# Board.net
KiCad netlist of a schematic drawn in Altium Designer
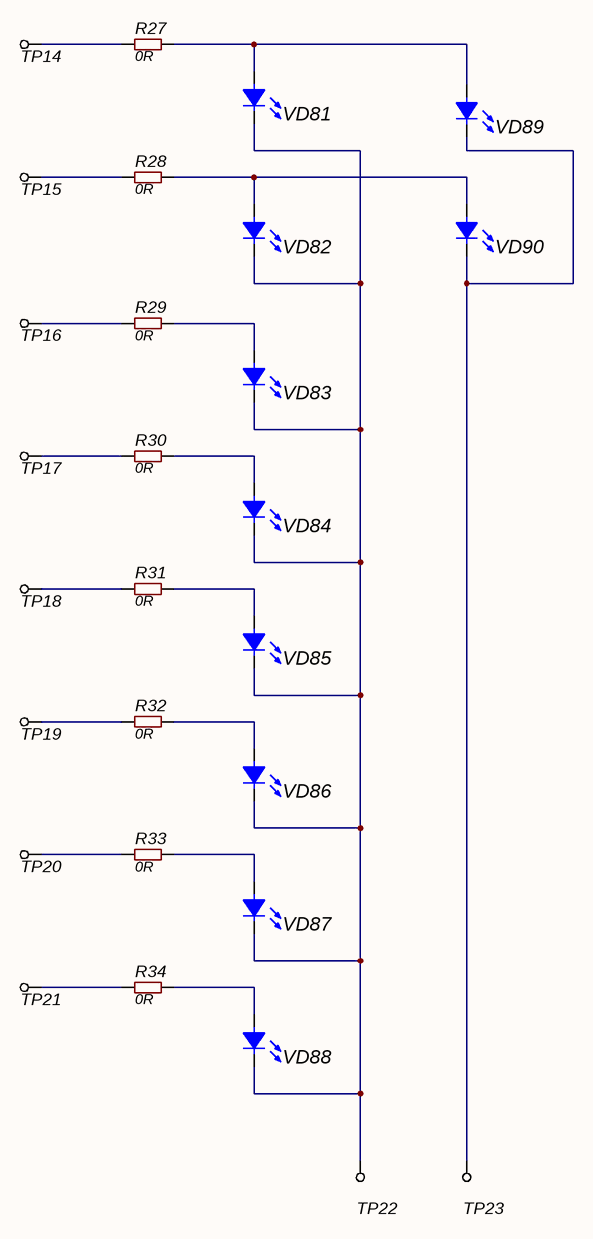
[diagram p0: Board.SchDoc]

(export (version "E")
  (design (tool "Eeschema 10.0.6"))
  (components
    (comp (ref "R27")
      (value "0R")
      (footprint "RES: 0603")
      (fields
        (field (name "MANUFACTURER") "Yageo")
        (field (name "PARTNUMBER") "RC0603JR-07100RL")
        (field (name "VALUEMANUFACTURERPARTNUMBER") "Resistor film, 0R, , 0603, 0.1W, -55...+125°C")
      )
      (libsource (lib "resistor") (part "Resistor_0603"))
    )
    (comp (ref "R28")
      (value "0R")
      (footprint "RES: 0603")
      (fields
        (field (name "MANUFACTURER") "Yageo")
        (field (name "PARTNUMBER") "RC0603JR-07100RL")
        (field (name "VALUEMANUFACTURERPARTNUMBER") "Resistor film, 0R, , 0603, 0.1W, -55...+125°C")
      )
      (libsource (lib "resistor") (part "Resistor_0603"))
    )
    (comp (ref "R29")
      (value "0R")
      (footprint "RES: 0603")
      (fields
        (field (name "MANUFACTURER") "Yageo")
        (field (name "PARTNUMBER") "RC0603JR-07100RL")
        (field (name "VALUEMANUFACTURERPARTNUMBER") "Resistor film, 0R, , 0603, 0.1W, -55...+125°C")
      )
      (libsource (lib "resistor") (part "Resistor_0603"))
    )
    (comp (ref "R30")
      (value "0R")
      (footprint "RES: 0603")
      (fields
        (field (name "MANUFACTURER") "Yageo")
        (field (name "PARTNUMBER") "RC0603JR-07100RL")
        (field (name "VALUEMANUFACTURERPARTNUMBER") "Resistor film, 0R, , 0603, 0.1W, -55...+125°C")
      )
      (libsource (lib "resistor") (part "Resistor_0603"))
    )
    (comp (ref "R31")
      (value "0R")
      (footprint "RES: 0603")
      (fields
        (field (name "MANUFACTURER") "Yageo")
        (field (name "PARTNUMBER") "RC0603JR-07100RL")
        (field (name "VALUEMANUFACTURERPARTNUMBER") "Resistor film, 0R, , 0603, 0.1W, -55...+125°C")
      )
      (libsource (lib "resistor") (part "Resistor_0603"))
    )
    (comp (ref "R32")
      (value "0R")
      (footprint "RES: 0603")
      (fields
        (field (name "MANUFACTURER") "Yageo")
        (field (name "PARTNUMBER") "RC0603JR-07100RL")
        (field (name "VALUEMANUFACTURERPARTNUMBER") "Resistor film, 0R, , 0603, 0.1W, -55...+125°C")
      )
      (libsource (lib "resistor") (part "Resistor_0603"))
    )
    (comp (ref "R33")
      (value "0R")
      (footprint "RES: 0603")
      (fields
        (field (name "MANUFACTURER") "Yageo")
        (field (name "PARTNUMBER") "RC0603JR-07100RL")
        (field (name "VALUEMANUFACTURERPARTNUMBER") "Resistor film, 0R, , 0603, 0.1W, -55...+125°C")
      )
      (libsource (lib "resistor") (part "Resistor_0603"))
    )
    (comp (ref "R34")
      (value "0R")
      (footprint "RES: 0603")
      (fields
        (field (name "MANUFACTURER") "Yageo")
        (field (name "PARTNUMBER") "RC0603JR-07100RL")
        (field (name "VALUEMANUFACTURERPARTNUMBER") "Resistor film, 0R, , 0603, 0.1W, -55...+125°C")
      )
      (libsource (lib "resistor") (part "Resistor_0603"))
    )
    (comp (ref "TP14")
      (value "Testpoint_HS1mm")
      (footprint "TestPoint(without 3D)")
      (libsource (lib "connector") (part "Testpoint_HS1mm"))
    )
    (comp (ref "TP15")
      (value "Testpoint_HS1mm")
      (footprint "TestPoint(without 3D)")
      (libsource (lib "connector") (part "Testpoint_HS1mm"))
    )
    (comp (ref "TP16")
      (value "Testpoint_HS1mm")
      (footprint "TestPoint(without 3D)")
      (libsource (lib "connector") (part "Testpoint_HS1mm"))
    )
    (comp (ref "TP17")
      (value "Testpoint_HS1mm")
      (footprint "TestPoint(without 3D)")
      (libsource (lib "connector") (part "Testpoint_HS1mm"))
    )
    (comp (ref "TP18")
      (value "Testpoint_HS1mm")
      (footprint "TestPoint(without 3D)")
      (libsource (lib "connector") (part "Testpoint_HS1mm"))
    )
    (comp (ref "TP19")
      (value "Testpoint_HS1mm")
      (footprint "TestPoint(without 3D)")
      (libsource (lib "connector") (part "Testpoint_HS1mm"))
    )
    (comp (ref "TP20")
      (value "Testpoint_HS1mm")
      (footprint "TestPoint(without 3D)")
      (libsource (lib "connector") (part "Testpoint_HS1mm"))
    )
    (comp (ref "TP21")
      (value "Testpoint_HS1mm")
      (footprint "TestPoint(without 3D)")
      (libsource (lib "connector") (part "Testpoint_HS1mm"))
    )
    (comp (ref "TP22")
      (value "Testpoint_HS1mm")
      (footprint "TestPoint(without 3D)")
      (libsource (lib "connector") (part "Testpoint_HS1mm"))
    )
    (comp (ref "TP23")
      (value "Testpoint_HS1mm")
      (footprint "TestPoint(without 3D)")
      (libsource (lib "connector") (part "Testpoint_HS1mm"))
    )
    (comp (ref "VD81")
      (value "~")
      (footprint "LED: 1206Y")
      (fields (field (name "VALUEMANUFACTURERPARTNUMBER") "LED, Green, *, *, *, -55...+150°C"))
      (libsource (lib "diode") (part "LED_single"))
    )
    (comp (ref "VD82")
      (value "~")
      (footprint "LED: 1206Y")
      (fields (field (name "VALUEMANUFACTURERPARTNUMBER") "LED, Green, *, *, *, -55...+150°C"))
      (libsource (lib "diode") (part "LED_single"))
    )
    (comp (ref "VD83")
      (value "~")
      (footprint "LED: 1206Y")
      (fields (field (name "VALUEMANUFACTURERPARTNUMBER") "LED, Green, *, *, *, -55...+150°C"))
      (libsource (lib "diode") (part "LED_single"))
    )
    (comp (ref "VD84")
      (value "~")
      (footprint "LED: 1206Y")
      (fields (field (name "VALUEMANUFACTURERPARTNUMBER") "LED, Green, *, *, *, -55...+150°C"))
      (libsource (lib "diode") (part "LED_single"))
    )
    (comp (ref "VD85")
      (value "~")
      (footprint "LED: 1206Y")
      (fields (field (name "VALUEMANUFACTURERPARTNUMBER") "LED, Green, *, *, *, -55...+150°C"))
      (libsource (lib "diode") (part "LED_single"))
    )
    (comp (ref "VD86")
      (value "~")
      (footprint "LED: 1206Y")
      (fields (field (name "VALUEMANUFACTURERPARTNUMBER") "LED, Green, *, *, *, -55...+150°C"))
      (libsource (lib "diode") (part "LED_single"))
    )
    (comp (ref "VD87")
      (value "~")
      (footprint "LED: 1206Y")
      (fields (field (name "VALUEMANUFACTURERPARTNUMBER") "LED, Green, *, *, *, -55...+150°C"))
      (libsource (lib "diode") (part "LED_single"))
    )
    (comp (ref "VD88")
      (value "~")
      (footprint "LED: 1206Y")
      (fields (field (name "VALUEMANUFACTURERPARTNUMBER") "LED, Green, *, *, *, -55...+150°C"))
      (libsource (lib "diode") (part "LED_single"))
    )
    (comp (ref "VD89")
      (value "~")
      (footprint "LED: 1206Y")
      (fields (field (name "VALUEMANUFACTURERPARTNUMBER") "LED, Green, *, *, *, -55...+150°C"))
      (libsource (lib "diode") (part "LED_single"))
    )
    (comp (ref "VD90")
      (value "~")
      (footprint "LED: 1206Y")
      (fields (field (name "VALUEMANUFACTURERPARTNUMBER") "LED, Green, *, *, *, -55...+150°C"))
      (libsource (lib "diode") (part "LED_single"))
    )
  )
  (nets
    (net (code "1") (name "Net-(R27-Pad1)") (class "Default")
      (node (ref "R27") (pin "1") (pinfunction "1_1") (pintype "passive"))
      (node (ref "TP14") (pin "1") (pinfunction "1_1") (pintype "passive"))
    )
    (net (code "2") (name "Net-(R28-Pad1)") (class "Default")
      (node (ref "R28") (pin "1") (pinfunction "1_1") (pintype "passive"))
      (node (ref "TP15") (pin "1") (pinfunction "1_1") (pintype "passive"))
    )
    (net (code "3") (name "Net-(R29-Pad1)") (class "Default")
      (node (ref "R29") (pin "1") (pinfunction "1_1") (pintype "passive"))
      (node (ref "TP16") (pin "1") (pinfunction "1_1") (pintype "passive"))
    )
    (net (code "4") (name "Net-(R30-Pad1)") (class "Default")
      (node (ref "R30") (pin "1") (pinfunction "1_1") (pintype "passive"))
      (node (ref "TP17") (pin "1") (pinfunction "1_1") (pintype "passive"))
    )
    (net (code "5") (name "Net-(R31-Pad1)") (class "Default")
      (node (ref "R31") (pin "1") (pinfunction "1_1") (pintype "passive"))
      (node (ref "TP18") (pin "1") (pinfunction "1_1") (pintype "passive"))
    )
    (net (code "6") (name "Net-(R32-Pad1)") (class "Default")
      (node (ref "R32") (pin "1") (pinfunction "1_1") (pintype "passive"))
      (node (ref "TP19") (pin "1") (pinfunction "1_1") (pintype "passive"))
    )
    (net (code "7") (name "Net-(R33-Pad1)") (class "Default")
      (node (ref "R33") (pin "1") (pinfunction "1_1") (pintype "passive"))
      (node (ref "TP20") (pin "1") (pinfunction "1_1") (pintype "passive"))
    )
    (net (code "8") (name "Net-(R34-Pad1)") (class "Default")
      (node (ref "R34") (pin "1") (pinfunction "1_1") (pintype "passive"))
      (node (ref "TP21") (pin "1") (pinfunction "1_1") (pintype "passive"))
    )
    (net (code "9") (name "Net-(VD81-A)") (class "Default")
      (node (ref "R27") (pin "2") (pinfunction "2_2") (pintype "passive"))
      (node (ref "VD81") (pin "1") (pinfunction "A_1") (pintype "passive"))
      (node (ref "VD89") (pin "1") (pinfunction "A_1") (pintype "passive"))
    )
    (net (code "10") (name "Net-(VD81-C)") (class "Default")
      (node (ref "TP22") (pin "1") (pinfunction "1_1") (pintype "passive"))
      (node (ref "VD81") (pin "2") (pinfunction "C_2") (pintype "passive"))
      (node (ref "VD82") (pin "2") (pinfunction "C_2") (pintype "passive"))
      (node (ref "VD83") (pin "2") (pinfunction "C_2") (pintype "passive"))
      (node (ref "VD84") (pin "2") (pinfunction "C_2") (pintype "passive"))
      (node (ref "VD85") (pin "2") (pinfunction "C_2") (pintype "passive"))
      (node (ref "VD86") (pin "2") (pinfunction "C_2") (pintype "passive"))
      (node (ref "VD87") (pin "2") (pinfunction "C_2") (pintype "passive"))
      (node (ref "VD88") (pin "2") (pinfunction "C_2") (pintype "passive"))
    )
    (net (code "11") (name "Net-(VD82-A)") (class "Default")
      (node (ref "R28") (pin "2") (pinfunction "2_2") (pintype "passive"))
      (node (ref "VD82") (pin "1") (pinfunction "A_1") (pintype "passive"))
      (node (ref "VD90") (pin "1") (pinfunction "A_1") (pintype "passive"))
    )
    (net (code "12") (name "Net-(VD83-A)") (class "Default")
      (node (ref "R29") (pin "2") (pinfunction "2_2") (pintype "passive"))
      (node (ref "VD83") (pin "1") (pinfunction "A_1") (pintype "passive"))
    )
    (net (code "13") (name "Net-(VD84-A)") (class "Default")
      (node (ref "R30") (pin "2") (pinfunction "2_2") (pintype "passive"))
      (node (ref "VD84") (pin "1") (pinfunction "A_1") (pintype "passive"))
    )
    (net (code "14") (name "Net-(VD85-A)") (class "Default")
      (node (ref "R31") (pin "2") (pinfunction "2_2") (pintype "passive"))
      (node (ref "VD85") (pin "1") (pinfunction "A_1") (pintype "passive"))
    )
    (net (code "15") (name "Net-(VD86-A)") (class "Default")
      (node (ref "R32") (pin "2") (pinfunction "2_2") (pintype "passive"))
      (node (ref "VD86") (pin "1") (pinfunction "A_1") (pintype "passive"))
    )
    (net (code "16") (name "Net-(VD87-A)") (class "Default")
      (node (ref "R33") (pin "2") (pinfunction "2_2") (pintype "passive"))
      (node (ref "VD87") (pin "1") (pinfunction "A_1") (pintype "passive"))
    )
    (net (code "17") (name "Net-(VD88-A)") (class "Default")
      (node (ref "R34") (pin "2") (pinfunction "2_2") (pintype "passive"))
      (node (ref "VD88") (pin "1") (pinfunction "A_1") (pintype "passive"))
    )
    (net (code "18") (name "Net-(VD89-C)") (class "Default")
      (node (ref "TP23") (pin "1") (pinfunction "1_1") (pintype "passive"))
      (node (ref "VD89") (pin "2") (pinfunction "C_2") (pintype "passive"))
      (node (ref "VD90") (pin "2") (pinfunction "C_2") (pintype "passive"))
    )
  )
)
